# ft232.net
KiCad netlist of a schematic drawn in Altium Designer
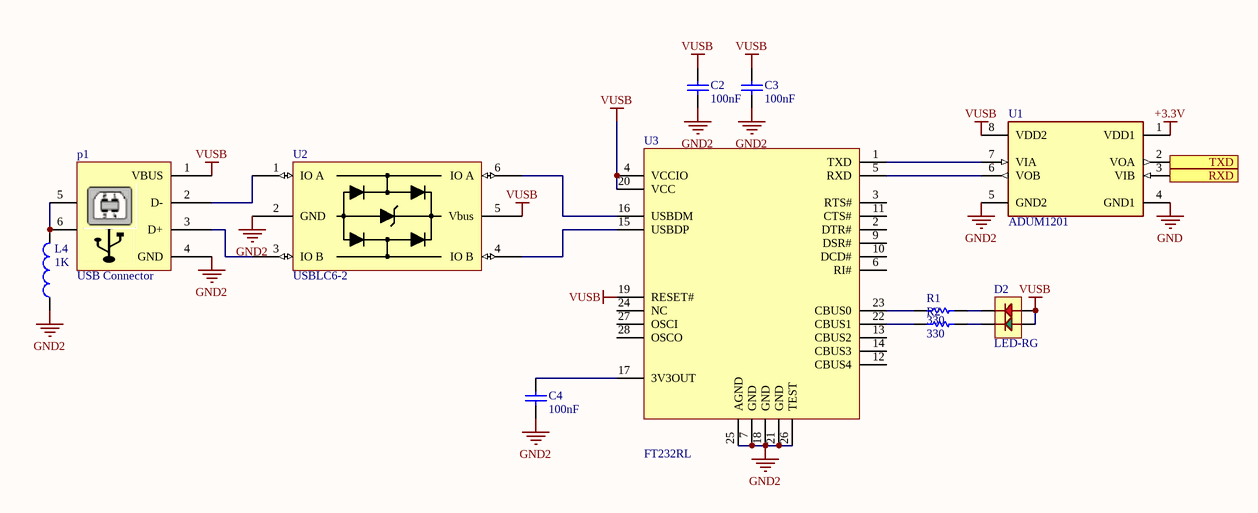
[diagram p0: ft232.SchDoc]

(export (version "E")
  (design (tool "Eeschema 10.0.6"))
  (components
    (comp (ref "C2")
      (value "100nF")
      (footprint "C805")
      (description "Capacitor")
      (fields (field (name "DESIGNER") "Parsa Malekpour"))
      (libsource (lib "ParsaLibrary") (part "Cap"))
    )
    (comp (ref "C3")
      (value "100nF")
      (footprint "C805")
      (description "Capacitor")
      (fields (field (name "DESIGNER") "Parsa Malekpour"))
      (libsource (lib "ParsaLibrary") (part "Cap"))
    )
    (comp (ref "C4")
      (value "100nF")
      (footprint "C805")
      (description "Capacitor")
      (fields (field (name "DESIGNER") "Parsa Malekpour"))
      (libsource (lib "ParsaLibrary") (part "Cap"))
    )
    (comp (ref "D2")
      (value "LED-RG")
      (footprint "LED-1210")
      (libsource (lib "ParsaLibrary") (part "LED-RG-4"))
    )
    (comp (ref "L4")
      (value "1K")
      (footprint "r805")
      (description "FERRITE BEAD")
      (fields (field (name "PUBLISHER") "Altium Limited"))
      (libsource (lib "ParsaLibrary") (part "Ferrite Bead"))
    )
    (comp (ref "p1")
      (value "USB Connector")
      (footprint "USB2-B-R")
      (description "USB Connector-B Type")
      (fields (field (name "DESIGNER") "Eng. Saeid Jorablo"))
      (libsource (lib "ParsaLibrary") (part "USB2-B"))
    )
    (comp (ref "R1")
      (value "330")
      (footprint "R0603")
      (description "Resistor")
      (fields (field (name "DESIGNER") "Parsa Malekpour"))
      (libsource (lib "ParsaLibrary") (part "Resistor"))
    )
    (comp (ref "R2")
      (value "330")
      (footprint "R0603")
      (description "Resistor")
      (fields (field (name "DESIGNER") "Parsa Malekpour"))
      (libsource (lib "ParsaLibrary") (part "Resistor"))
    )
    (comp (ref "U1")
      (value "ADUM1201")
      (footprint "soic-8n")
      (description "Dual-Channel Digital Isolators")
      (fields (field (name "MF") "{'manufacturer': u'Analog Devices'}") (field (name "MP") "ADUM1201AR"))
      (libsource (lib "ParsaLibrary") (part "ADUM1201"))
    )
    (comp (ref "U2")
      (value "USBLC6-2")
      (footprint "SOT-23-6")
      (description "Very low capacitance ESD protection")
      (libsource (lib "ParsaLibrary") (part "USBLC6-2"))
    )
    (comp (ref "U3")
      (value "FT232RL")
      (footprint "SSOP-28N")
      (libsource (lib "ParsaLibrary") (part "FT232RL"))
    )
  )
  (nets
    (net (code "1") (name "+3.3V") (class "Default")
      (node (ref "U1") (pin "1") (pinfunction "VDD1_1") (pintype "power_in"))
    )
    (net (code "2") (name "/RXD") (class "Default")
      (node (ref "U1") (pin "3") (pinfunction "VIB_3") (pintype "input"))
    )
    (net (code "3") (name "/TXD") (class "Default")
      (node (ref "U1") (pin "2") (pinfunction "VOA_2") (pintype "output"))
    )
    (net (code "4") (name "GND") (class "Default")
      (node (ref "U1") (pin "4") (pinfunction "GND1_4") (pintype "passive"))
    )
    (net (code "5") (name "GND2") (class "Default")
      (node (ref "C2") (pin "1") (pinfunction "1_1") (pintype "passive"))
      (node (ref "C3") (pin "1") (pinfunction "1_1") (pintype "passive"))
      (node (ref "C4") (pin "1") (pinfunction "1_1") (pintype "passive"))
      (node (ref "L4") (pin "1") (pinfunction "1_1") (pintype "passive"))
      (node (ref "U1") (pin "5") (pinfunction "GND2_5") (pintype "passive"))
      (node (ref "U2") (pin "2") (pinfunction "GND_2") (pintype "power_in"))
      (node (ref "U3") (pin "18") (pinfunction "GND_18") (pintype "passive"))
      (node (ref "U3") (pin "21") (pinfunction "GND_21") (pintype "passive"))
      (node (ref "U3") (pin "25") (pinfunction "AGND_25") (pintype "passive"))
      (node (ref "U3") (pin "26") (pinfunction "TEST_26") (pintype "passive"))
      (node (ref "U3") (pin "7") (pinfunction "GND_7") (pintype "passive"))
      (node (ref "p1") (pin "4") (pinfunction "GND_4") (pintype "power_in"))
    )
    (net (code "6") (name "Net-(D2-GRN-C)") (class "Default")
      (node (ref "D2") (pin "4") (pinfunction "GRN-C_4") (pintype "passive"))
      (node (ref "R2") (pin "2") (pinfunction "2_2") (pintype "passive"))
    )
    (net (code "7") (name "Net-(D2-RED-C)") (class "Default")
      (node (ref "D2") (pin "3") (pinfunction "RED-C_3") (pintype "passive"))
      (node (ref "R1") (pin "2") (pinfunction "2_2") (pintype "passive"))
    )
    (net (code "8") (name "Net-(L4-Pad2)") (class "Default")
      (node (ref "L4") (pin "2") (pinfunction "2_2") (pintype "passive"))
      (node (ref "p1") (pin "5") (pinfunction "5_5") (pintype "passive"))
      (node (ref "p1") (pin "6") (pinfunction "6_6") (pintype "passive"))
    )
    (net (code "9") (name "Net-(U1-VIA)") (class "Default")
      (node (ref "U1") (pin "7") (pinfunction "VIA_7") (pintype "input"))
      (node (ref "U3") (pin "1") (pinfunction "TXD_1") (pintype "passive"))
    )
    (net (code "10") (name "Net-(U1-VOB)") (class "Default")
      (node (ref "U1") (pin "6") (pinfunction "VOB_6") (pintype "output"))
      (node (ref "U3") (pin "5") (pinfunction "RXD_5") (pintype "passive"))
    )
    (net (code "11") (name "Net-(U3-3V3OUT)") (class "Default")
      (node (ref "C4") (pin "2") (pinfunction "2_2") (pintype "passive"))
      (node (ref "U3") (pin "17") (pinfunction "3V3OUT_17") (pintype "passive"))
    )
    (net (code "12") (name "Net-(U3-CBUS0)") (class "Default")
      (node (ref "R1") (pin "1") (pinfunction "1_1") (pintype "passive"))
      (node (ref "U3") (pin "23") (pinfunction "CBUS0_23") (pintype "passive"))
    )
    (net (code "13") (name "Net-(U3-CBUS1)") (class "Default")
      (node (ref "R2") (pin "1") (pinfunction "1_1") (pintype "passive"))
      (node (ref "U3") (pin "22") (pinfunction "CBUS1_22") (pintype "passive"))
    )
    (net (code "14") (name "Net-(U3-USBDM)") (class "Default")
      (node (ref "U2") (pin "6") (pinfunction "IO_A_6") (pintype "bidirectional"))
      (node (ref "U3") (pin "16") (pinfunction "USBDM_16") (pintype "passive"))
    )
    (net (code "15") (name "Net-(U3-USBDP)") (class "Default")
      (node (ref "U2") (pin "4") (pinfunction "IO_B_4") (pintype "bidirectional"))
      (node (ref "U3") (pin "15") (pinfunction "USBDP_15") (pintype "passive"))
    )
    (net (code "16") (name "Net-(p1-D+)") (class "Default")
      (node (ref "U2") (pin "3") (pinfunction "IO_B_3") (pintype "bidirectional"))
      (node (ref "p1") (pin "3") (pinfunction "D+_3") (pintype "passive"))
    )
    (net (code "17") (name "Net-(p1-D-)") (class "Default")
      (node (ref "U2") (pin "1") (pinfunction "IO_A_1") (pintype "bidirectional"))
      (node (ref "p1") (pin "2") (pinfunction "D-_2") (pintype "passive"))
    )
    (net (code "18") (name "VUSB") (class "Default")
      (node (ref "C2") (pin "2") (pinfunction "2_2") (pintype "passive"))
      (node (ref "C3") (pin "2") (pinfunction "2_2") (pintype "passive"))
      (node (ref "D2") (pin "1") (pinfunction "GRN-A_1") (pintype "passive"))
      (node (ref "D2") (pin "2") (pinfunction "RED-A_2") (pintype "passive"))
      (node (ref "U1") (pin "8") (pinfunction "VDD2_8") (pintype "power_in"))
      (node (ref "U2") (pin "5") (pinfunction "Vbus_5") (pintype "power_in"))
      (node (ref "U3") (pin "19") (pinfunction "RESET#_19") (pintype "passive"))
      (node (ref "U3") (pin "20") (pinfunction "VCC_20") (pintype "passive"))
      (node (ref "U3") (pin "4") (pinfunction "VCCIO_4") (pintype "passive"))
      (node (ref "p1") (pin "1") (pinfunction "VBUS_1") (pintype "power_in"))
    )
    (net (code "19") (name "unconnected-(U3-CBUS2-Pad13)") (class "Default")
      (node (ref "U3") (pin "13") (pinfunction "CBUS2_13") (pintype "passive"))
    )
    (net (code "20") (name "unconnected-(U3-CBUS3-Pad14)") (class "Default")
      (node (ref "U3") (pin "14") (pinfunction "CBUS3_14") (pintype "passive"))
    )
    (net (code "21") (name "unconnected-(U3-CBUS4-Pad12)") (class "Default")
      (node (ref "U3") (pin "12") (pinfunction "CBUS4_12") (pintype "passive"))
    )
    (net (code "22") (name "unconnected-(U3-CTS#-Pad11)") (class "Default")
      (node (ref "U3") (pin "11") (pinfunction "CTS#_11") (pintype "passive"))
    )
    (net (code "23") (name "unconnected-(U3-DCD#-Pad10)") (class "Default")
      (node (ref "U3") (pin "10") (pinfunction "DCD#_10") (pintype "passive"))
    )
    (net (code "24") (name "unconnected-(U3-DSR#-Pad9)") (class "Default")
      (node (ref "U3") (pin "9") (pinfunction "DSR#_9") (pintype "passive"))
    )
    (net (code "25") (name "unconnected-(U3-DTR#-Pad2)") (class "Default")
      (node (ref "U3") (pin "2") (pinfunction "DTR#_2") (pintype "passive"))
    )
    (net (code "26") (name "unconnected-(U3-NC-Pad8)") (class "Default")
      (node (ref "U3") (pin "8") (pinfunction "NC_8") (pintype "passive"))
    )
    (net (code "27") (name "unconnected-(U3-NC-Pad24)") (class "Default")
      (node (ref "U3") (pin "24") (pinfunction "NC_24") (pintype "passive"))
    )
    (net (code "28") (name "unconnected-(U3-OSCI-Pad27)") (class "Default")
      (node (ref "U3") (pin "27") (pinfunction "OSCI_27") (pintype "passive"))
    )
    (net (code "29") (name "unconnected-(U3-OSCO-Pad28)") (class "Default")
      (node (ref "U3") (pin "28") (pinfunction "OSCO_28") (pintype "passive"))
    )
    (net (code "30") (name "unconnected-(U3-RI#-Pad6)") (class "Default")
      (node (ref "U3") (pin "6") (pinfunction "RI#_6") (pintype "passive"))
    )
    (net (code "31") (name "unconnected-(U3-RTS#-Pad3)") (class "Default")
      (node (ref "U3") (pin "3") (pinfunction "RTS#_3") (pintype "passive"))
    )
  )
)
